# one_led.net
KiCad netlist of a schematic drawn in EAGLE
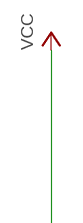
[diagram p0: schematic, sheet 1, part 1 of 2]
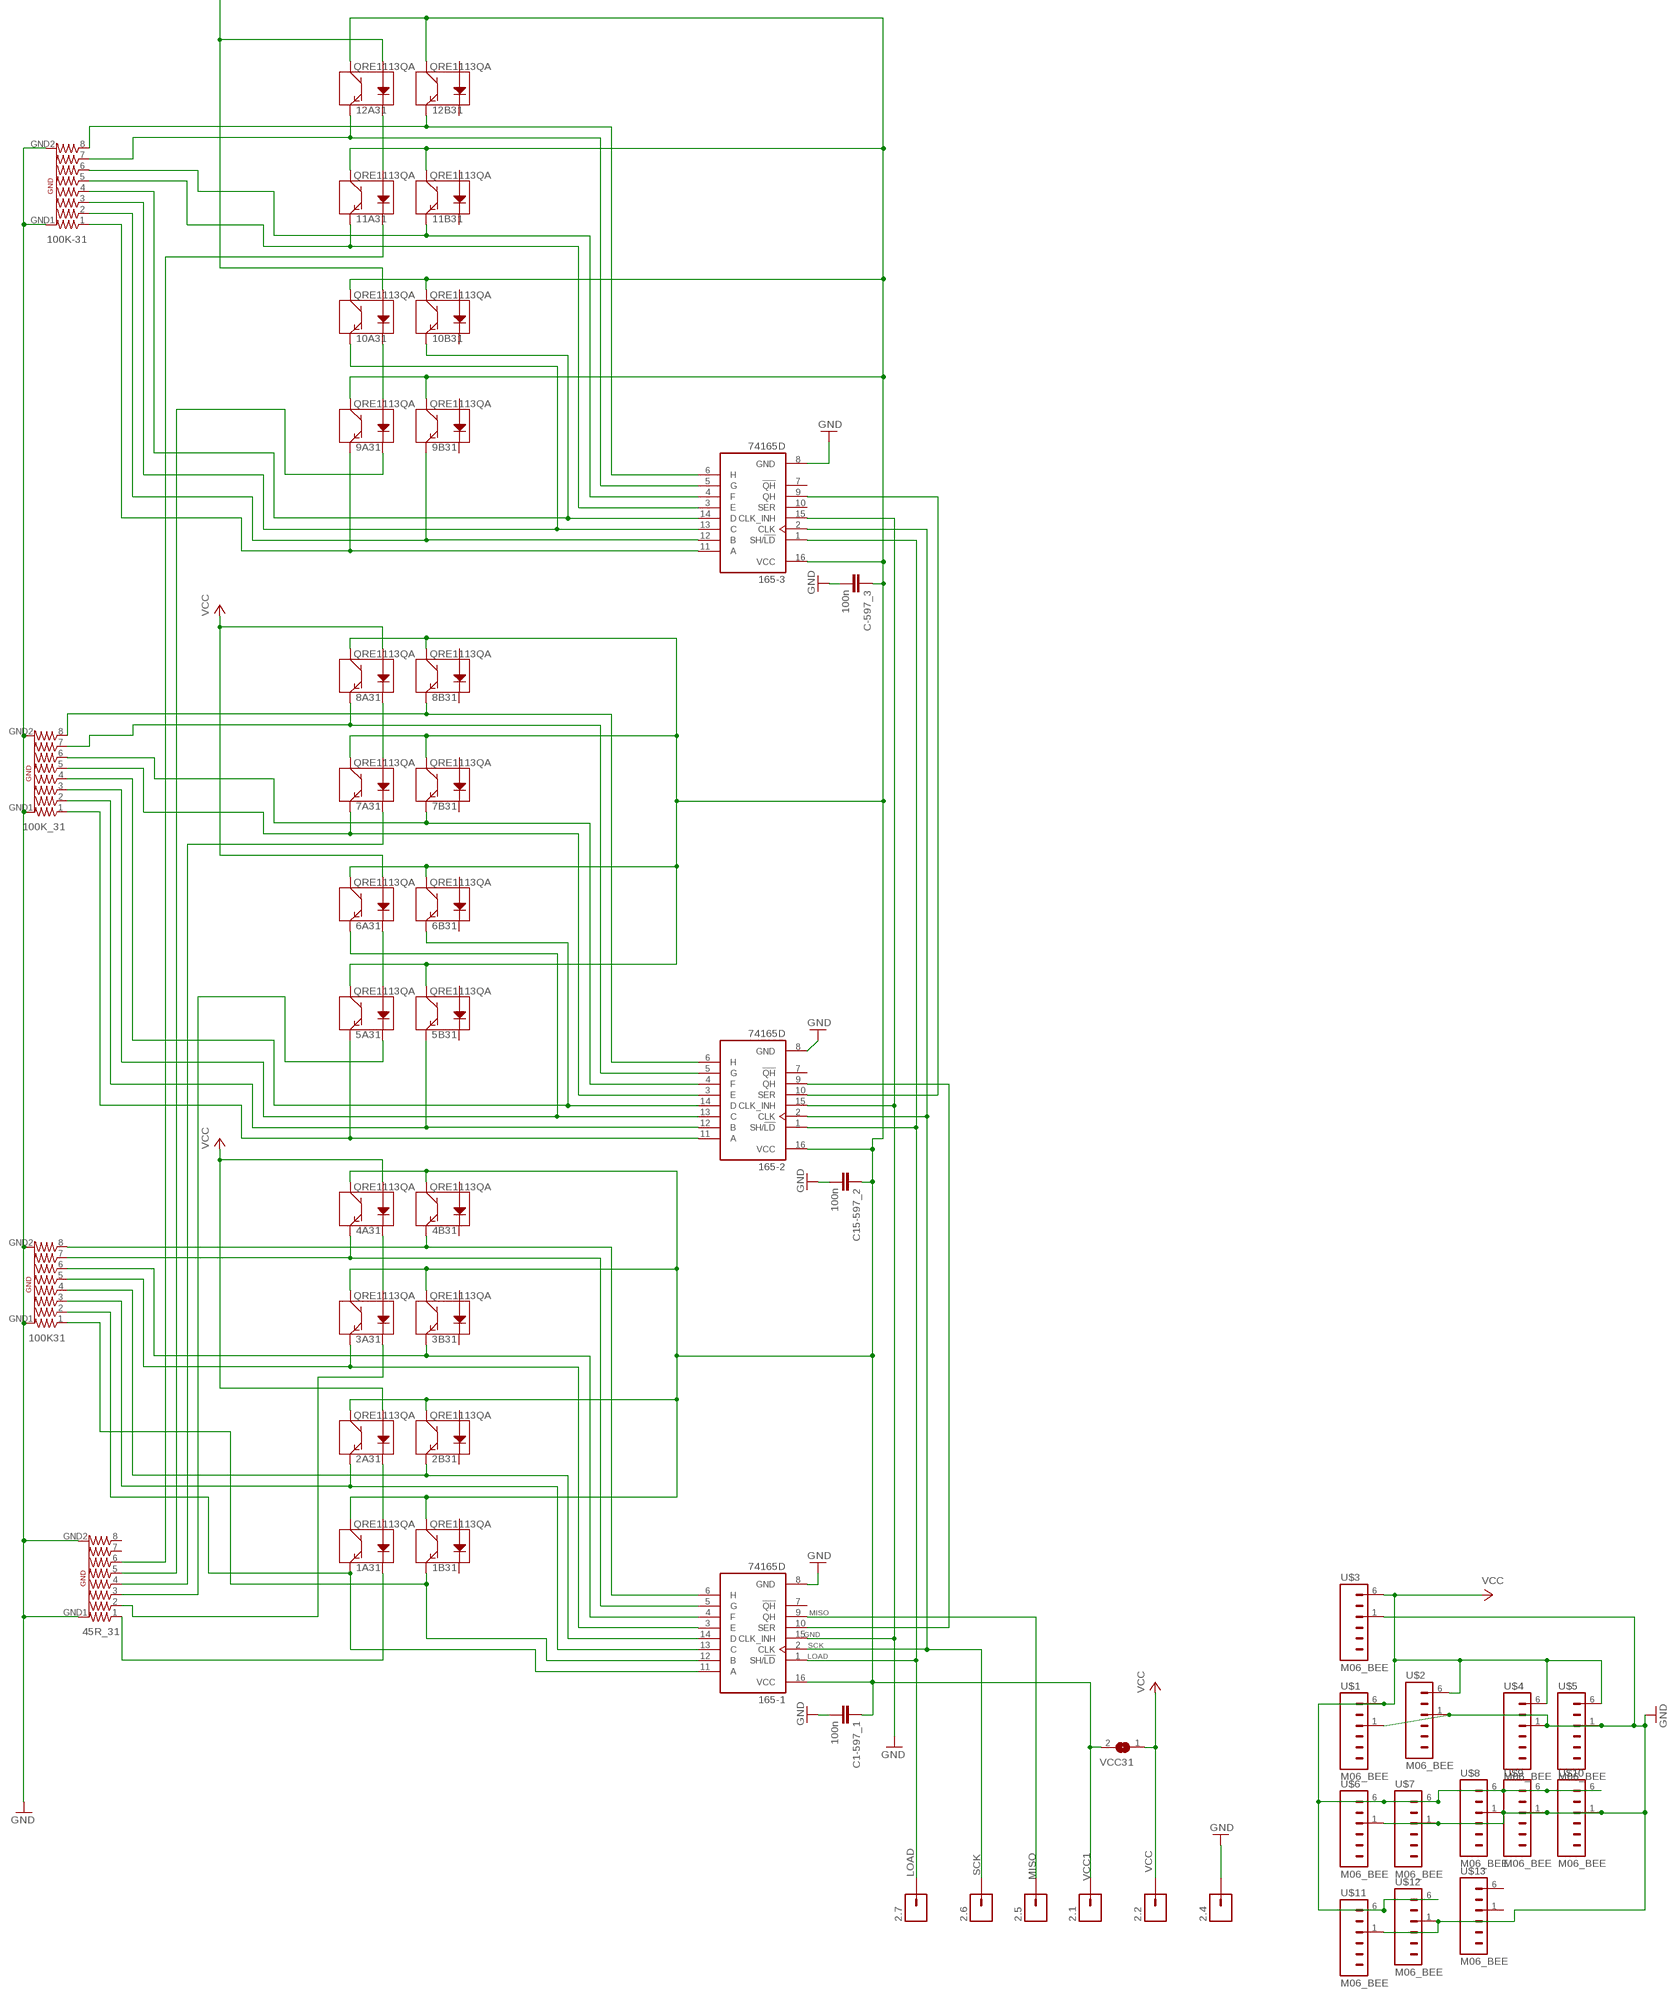
[diagram p1: schematic, sheet 1, part 2 of 2]

(export (version "E")
  (design (tool "Eeschema 10.0.6"))
  (components
    (comp (ref "1A31")
      (value "QRE1113QA")
      (footprint "eagle-import:QRE1113")
      (libsource (lib "eagle-import") (part "QRE1113QA"))
    )
    (comp (ref "1B31")
      (value "QRE1113QA")
      (footprint "eagle-import:QRE1113")
      (libsource (lib "eagle-import") (part "QRE1113QA"))
    )
    (comp (ref "2.1")
      (value "M01ADN")
      (footprint "eagle-import:1X01-16GAUGE")
      (libsource (lib "eagle-import") (part "M01ADN"))
    )
    (comp (ref "2.2")
      (value "M01ADN")
      (footprint "eagle-import:1X01-16GAUGE")
      (libsource (lib "eagle-import") (part "M01ADN"))
    )
    (comp (ref "2.4")
      (value "M01ADN")
      (footprint "eagle-import:1X01-16GAUGE")
      (libsource (lib "eagle-import") (part "M01ADN"))
    )
    (comp (ref "2.5")
      (value "M01ADN")
      (footprint "eagle-import:1X01-16GAUGE")
      (libsource (lib "eagle-import") (part "M01ADN"))
    )
    (comp (ref "2.6")
      (value "M01ADN")
      (footprint "eagle-import:1X01-16GAUGE")
      (libsource (lib "eagle-import") (part "M01ADN"))
    )
    (comp (ref "2.7")
      (value "M01ADN")
      (footprint "eagle-import:1X01-16GAUGE")
      (libsource (lib "eagle-import") (part "M01ADN"))
    )
    (comp (ref "2A31")
      (value "QRE1113QA")
      (footprint "eagle-import:QRE1113")
      (libsource (lib "eagle-import") (part "QRE1113QA"))
    )
    (comp (ref "2B31")
      (value "QRE1113QA")
      (footprint "eagle-import:QRE1113")
      (libsource (lib "eagle-import") (part "QRE1113QA"))
    )
    (comp (ref "3A31")
      (value "QRE1113QA")
      (footprint "eagle-import:QRE1113")
      (libsource (lib "eagle-import") (part "QRE1113QA"))
    )
    (comp (ref "3B31")
      (value "QRE1113QA")
      (footprint "eagle-import:QRE1113")
      (libsource (lib "eagle-import") (part "QRE1113QA"))
    )
    (comp (ref "4A31")
      (value "QRE1113QA")
      (footprint "eagle-import:QRE1113")
      (libsource (lib "eagle-import") (part "QRE1113QA"))
    )
    (comp (ref "4B31")
      (value "QRE1113QA")
      (footprint "eagle-import:QRE1113")
      (libsource (lib "eagle-import") (part "QRE1113QA"))
    )
    (comp (ref "5A31")
      (value "QRE1113QA")
      (footprint "eagle-import:QRE1113")
      (libsource (lib "eagle-import") (part "QRE1113QA"))
    )
    (comp (ref "5B31")
      (value "QRE1113QA")
      (footprint "eagle-import:QRE1113")
      (libsource (lib "eagle-import") (part "QRE1113QA"))
    )
    (comp (ref "6A31")
      (value "QRE1113QA")
      (footprint "eagle-import:QRE1113")
      (libsource (lib "eagle-import") (part "QRE1113QA"))
    )
    (comp (ref "6B31")
      (value "QRE1113QA")
      (footprint "eagle-import:QRE1113")
      (libsource (lib "eagle-import") (part "QRE1113QA"))
    )
    (comp (ref "7A31")
      (value "QRE1113QA")
      (footprint "eagle-import:QRE1113")
      (libsource (lib "eagle-import") (part "QRE1113QA"))
    )
    (comp (ref "7B31")
      (value "QRE1113QA")
      (footprint "eagle-import:QRE1113")
      (libsource (lib "eagle-import") (part "QRE1113QA"))
    )
    (comp (ref "8A31")
      (value "QRE1113QA")
      (footprint "eagle-import:QRE1113")
      (libsource (lib "eagle-import") (part "QRE1113QA"))
    )
    (comp (ref "8B31")
      (value "QRE1113QA")
      (footprint "eagle-import:QRE1113")
      (libsource (lib "eagle-import") (part "QRE1113QA"))
    )
    (comp (ref "9A31")
      (value "QRE1113QA")
      (footprint "eagle-import:QRE1113")
      (libsource (lib "eagle-import") (part "QRE1113QA"))
    )
    (comp (ref "9B31")
      (value "QRE1113QA")
      (footprint "eagle-import:QRE1113")
      (libsource (lib "eagle-import") (part "QRE1113QA"))
    )
    (comp (ref "10A31")
      (value "QRE1113QA")
      (footprint "eagle-import:QRE1113")
      (libsource (lib "eagle-import") (part "QRE1113QA"))
    )
    (comp (ref "10B31")
      (value "QRE1113QA")
      (footprint "eagle-import:QRE1113")
      (libsource (lib "eagle-import") (part "QRE1113QA"))
    )
    (comp (ref "11A31")
      (value "QRE1113QA")
      (footprint "eagle-import:QRE1113")
      (libsource (lib "eagle-import") (part "QRE1113QA"))
    )
    (comp (ref "11B31")
      (value "QRE1113QA")
      (footprint "eagle-import:QRE1113")
      (libsource (lib "eagle-import") (part "QRE1113QA"))
    )
    (comp (ref "12A31")
      (value "QRE1113QA")
      (footprint "eagle-import:QRE1113")
      (libsource (lib "eagle-import") (part "QRE1113QA"))
    )
    (comp (ref "12B31")
      (value "QRE1113QA")
      (footprint "eagle-import:QRE1113")
      (libsource (lib "eagle-import") (part "QRE1113QA"))
    )
    (comp (ref "45R_31")
      (value "RESISTOR-ARRAY_BUSSED")
      (footprint "eagle-import:1608_ARRAY")
      (libsource (lib "eagle-import") (part "RESISTOR-ARRAY_BUSSED"))
    )
    (comp (ref "100K-31")
      (value "RESISTOR-ARRAY_BUSSED")
      (footprint "eagle-import:1608_ARRAY")
      (libsource (lib "eagle-import") (part "RESISTOR-ARRAY_BUSSED"))
    )
    (comp (ref "100K31")
      (value "RESISTOR-ARRAY_BUSSED")
      (footprint "eagle-import:1608_ARRAY")
      (libsource (lib "eagle-import") (part "RESISTOR-ARRAY_BUSSED"))
    )
    (comp (ref "100K_31")
      (value "RESISTOR-ARRAY_BUSSED")
      (footprint "eagle-import:1608_ARRAY")
      (libsource (lib "eagle-import") (part "RESISTOR-ARRAY_BUSSED"))
    )
    (comp (ref "165-1")
      (value "74165D")
      (footprint "eagle-import:SO16")
      (libsource (lib "eagle-import") (part "74165D"))
    )
    (comp (ref "165-2")
      (value "74165D")
      (footprint "eagle-import:SO16")
      (libsource (lib "eagle-import") (part "74165D"))
    )
    (comp (ref "165-3")
      (value "74165D")
      (footprint "eagle-import:SO16")
      (libsource (lib "eagle-import") (part "74165D"))
    )
    (comp (ref "C-597_3")
      (value "100n")
      (footprint "eagle-import:C0603")
      (libsource (lib "eagle-import") (part "C-EUC0603"))
    )
    (comp (ref "C1-597_1")
      (value "100n")
      (footprint "eagle-import:C0603")
      (libsource (lib "eagle-import") (part "C-EUC0603"))
    )
    (comp (ref "C15-597_2")
      (value "100n")
      (footprint "eagle-import:C0603")
      (libsource (lib "eagle-import") (part "C-EUC0603"))
    )
    (comp (ref "U$1")
      (value "M06_BEE")
      (footprint "eagle-import:1X06_BEE")
      (libsource (lib "eagle-import") (part "M06_BEE"))
    )
    (comp (ref "U$2")
      (value "M06_BEE")
      (footprint "eagle-import:1X06_BEE")
      (libsource (lib "eagle-import") (part "M06_BEE"))
    )
    (comp (ref "U$3")
      (value "M06_BEE")
      (footprint "eagle-import:1X06_BEE")
      (libsource (lib "eagle-import") (part "M06_BEE"))
    )
    (comp (ref "U$4")
      (value "M06_BEE")
      (footprint "eagle-import:1X06_BEE")
      (libsource (lib "eagle-import") (part "M06_BEE"))
    )
    (comp (ref "U$5")
      (value "M06_BEE")
      (footprint "eagle-import:1X06_BEE")
      (libsource (lib "eagle-import") (part "M06_BEE"))
    )
    (comp (ref "U$6")
      (value "M06_BEE")
      (footprint "eagle-import:1X06_BEE")
      (libsource (lib "eagle-import") (part "M06_BEE"))
    )
    (comp (ref "U$7")
      (value "M06_BEE")
      (footprint "eagle-import:1X06_BEE")
      (libsource (lib "eagle-import") (part "M06_BEE"))
    )
    (comp (ref "U$8")
      (value "M06_BEE")
      (footprint "eagle-import:1X06_BEE")
      (libsource (lib "eagle-import") (part "M06_BEE"))
    )
    (comp (ref "U$9")
      (value "M06_BEE")
      (footprint "eagle-import:1X06_BEE")
      (libsource (lib "eagle-import") (part "M06_BEE"))
    )
    (comp (ref "U$10")
      (value "M06_BEE")
      (footprint "eagle-import:1X06_BEE")
      (libsource (lib "eagle-import") (part "M06_BEE"))
    )
    (comp (ref "U$11")
      (value "M06_BEE")
      (footprint "eagle-import:1X06_BEE")
      (libsource (lib "eagle-import") (part "M06_BEE"))
    )
    (comp (ref "U$12")
      (value "M06_BEE")
      (footprint "eagle-import:1X06_BEE")
      (libsource (lib "eagle-import") (part "M06_BEE"))
    )
    (comp (ref "U$13")
      (value "M06_BEE")
      (footprint "eagle-import:1X06_BEE")
      (libsource (lib "eagle-import") (part "M06_BEE"))
    )
    (comp (ref "VCC31")
      (value "SJ")
      (footprint "eagle-import:SJ")
      (libsource (lib "eagle-import") (part "SJ"))
    )
  )
  (nets
    (net (code "1") (name "/LOAD") (class "Default")
      (node (ref "165-1") (pin "1") (pinfunction "SH/~{LD}_1") (pintype "input"))
      (node (ref "165-2") (pin "1") (pinfunction "SH/~{LD}_1") (pintype "input"))
      (node (ref "165-3") (pin "1") (pinfunction "SH/~{LD}_1") (pintype "input"))
      (node (ref "2.7") (pin "1") (pinfunction "1_1") (pintype "passive"))
    )
    (net (code "2") (name "/MISO") (class "Default")
      (node (ref "165-1") (pin "9") (pinfunction "QH_9") (pintype "tri_state"))
      (node (ref "2.5") (pin "1") (pinfunction "1_1") (pintype "passive"))
    )
    (net (code "3") (name "/SCK") (class "Default")
      (node (ref "165-1") (pin "2") (pinfunction "CLK_2") (pintype "input"))
      (node (ref "165-2") (pin "2") (pinfunction "CLK_2") (pintype "input"))
      (node (ref "165-3") (pin "2") (pinfunction "CLK_2") (pintype "input"))
      (node (ref "2.6") (pin "1") (pinfunction "1_1") (pintype "passive"))
    )
    (net (code "4") (name "/VCC1") (class "Default")
      (node (ref "10A31") (pin "3") (pinfunction "C_3") (pintype "bidirectional"))
      (node (ref "10B31") (pin "3") (pinfunction "C_3") (pintype "bidirectional"))
      (node (ref "11A31") (pin "3") (pinfunction "C_3") (pintype "bidirectional"))
      (node (ref "11B31") (pin "3") (pinfunction "C_3") (pintype "bidirectional"))
      (node (ref "12A31") (pin "3") (pinfunction "C_3") (pintype "bidirectional"))
      (node (ref "12B31") (pin "3") (pinfunction "C_3") (pintype "bidirectional"))
      (node (ref "165-1") (pin "16") (pinfunction "VCC_16") (pintype "power_in"))
      (node (ref "165-2") (pin "16") (pinfunction "VCC_16") (pintype "power_in"))
      (node (ref "165-3") (pin "16") (pinfunction "VCC_16") (pintype "power_in"))
      (node (ref "1A31") (pin "3") (pinfunction "C_3") (pintype "bidirectional"))
      (node (ref "1B31") (pin "3") (pinfunction "C_3") (pintype "bidirectional"))
      (node (ref "2.1") (pin "1") (pinfunction "1_1") (pintype "passive"))
      (node (ref "2A31") (pin "3") (pinfunction "C_3") (pintype "bidirectional"))
      (node (ref "2B31") (pin "3") (pinfunction "C_3") (pintype "bidirectional"))
      (node (ref "3A31") (pin "3") (pinfunction "C_3") (pintype "bidirectional"))
      (node (ref "3B31") (pin "3") (pinfunction "C_3") (pintype "bidirectional"))
      (node (ref "4A31") (pin "3") (pinfunction "C_3") (pintype "bidirectional"))
      (node (ref "4B31") (pin "3") (pinfunction "C_3") (pintype "bidirectional"))
      (node (ref "5A31") (pin "3") (pinfunction "C_3") (pintype "bidirectional"))
      (node (ref "5B31") (pin "3") (pinfunction "C_3") (pintype "bidirectional"))
      (node (ref "6A31") (pin "3") (pinfunction "C_3") (pintype "bidirectional"))
      (node (ref "6B31") (pin "3") (pinfunction "C_3") (pintype "bidirectional"))
      (node (ref "7A31") (pin "3") (pinfunction "C_3") (pintype "bidirectional"))
      (node (ref "7B31") (pin "3") (pinfunction "C_3") (pintype "bidirectional"))
      (node (ref "8A31") (pin "3") (pinfunction "C_3") (pintype "bidirectional"))
      (node (ref "8B31") (pin "3") (pinfunction "C_3") (pintype "bidirectional"))
      (node (ref "9A31") (pin "3") (pinfunction "C_3") (pintype "bidirectional"))
      (node (ref "9B31") (pin "3") (pinfunction "C_3") (pintype "bidirectional"))
      (node (ref "C-597_3") (pin "1") (pinfunction "1_1") (pintype "passive"))
      (node (ref "C1-597_1") (pin "1") (pinfunction "1_1") (pintype "passive"))
      (node (ref "C15-597_2") (pin "1") (pinfunction "1_1") (pintype "passive"))
      (node (ref "VCC31") (pin "2") (pinfunction "2_2") (pintype "passive"))
    )
    (net (code "5") (name "GND") (class "Default")
      (node (ref "100K-31") (pin "GND1") (pinfunction "GND1_GND1") (pintype "passive"))
      (node (ref "100K-31") (pin "GND2") (pinfunction "GND2_GND2") (pintype "passive"))
      (node (ref "100K31") (pin "GND1") (pinfunction "GND1_GND1") (pintype "passive"))
      (node (ref "100K31") (pin "GND2") (pinfunction "GND2_GND2") (pintype "passive"))
      (node (ref "100K_31") (pin "GND1") (pinfunction "GND1_GND1") (pintype "passive"))
      (node (ref "100K_31") (pin "GND2") (pinfunction "GND2_GND2") (pintype "passive"))
      (node (ref "165-1") (pin "15") (pinfunction "CLK_INH_15") (pintype "input"))
      (node (ref "165-1") (pin "8") (pinfunction "GND_8") (pintype "power_in"))
      (node (ref "165-2") (pin "15") (pinfunction "CLK_INH_15") (pintype "input"))
      (node (ref "165-2") (pin "8") (pinfunction "GND_8") (pintype "power_in"))
      (node (ref "165-3") (pin "15") (pinfunction "CLK_INH_15") (pintype "input"))
      (node (ref "165-3") (pin "8") (pinfunction "GND_8") (pintype "power_in"))
      (node (ref "2.4") (pin "1") (pinfunction "1_1") (pintype "passive"))
      (node (ref "45R_31") (pin "GND1") (pinfunction "GND1_GND1") (pintype "passive"))
      (node (ref "45R_31") (pin "GND2") (pinfunction "GND2_GND2") (pintype "passive"))
      (node (ref "C-597_3") (pin "2") (pinfunction "2_2") (pintype "passive"))
      (node (ref "C1-597_1") (pin "2") (pinfunction "2_2") (pintype "passive"))
      (node (ref "C15-597_2") (pin "2") (pinfunction "2_2") (pintype "passive"))
      (node (ref "U$1") (pin "1") (pinfunction "4_1") (pintype "passive"))
      (node (ref "U$10") (pin "1") (pinfunction "4_1") (pintype "passive"))
      (node (ref "U$11") (pin "1") (pinfunction "4_1") (pintype "passive"))
      (node (ref "U$12") (pin "1") (pinfunction "4_1") (pintype "passive"))
      (node (ref "U$2") (pin "1") (pinfunction "4_1") (pintype "passive"))
      (node (ref "U$3") (pin "1") (pinfunction "4_1") (pintype "passive"))
      (node (ref "U$4") (pin "1") (pinfunction "4_1") (pintype "passive"))
      (node (ref "U$5") (pin "1") (pinfunction "4_1") (pintype "passive"))
      (node (ref "U$6") (pin "1") (pinfunction "4_1") (pintype "passive"))
      (node (ref "U$7") (pin "1") (pinfunction "4_1") (pintype "passive"))
      (node (ref "U$8") (pin "1") (pinfunction "4_1") (pintype "passive"))
      (node (ref "U$9") (pin "1") (pinfunction "4_1") (pintype "passive"))
    )
    (net (code "6") (name "Net-(1A31-A)") (class "Default")
      (node (ref "1A31") (pin "1") (pinfunction "A_1") (pintype "bidirectional"))
      (node (ref "2A31") (pin "2") (pinfunction "K_2") (pintype "bidirectional"))
    )
    (net (code "7") (name "Net-(1A31-K)") (class "Default")
      (node (ref "1A31") (pin "2") (pinfunction "K_2") (pintype "bidirectional"))
      (node (ref "45R_31") (pin "1") (pinfunction "1_1") (pintype "passive"))
    )
    (net (code "8") (name "Net-(3A31-A)") (class "Default")
      (node (ref "3A31") (pin "1") (pinfunction "A_1") (pintype "bidirectional"))
      (node (ref "4A31") (pin "2") (pinfunction "K_2") (pintype "bidirectional"))
    )
    (net (code "9") (name "Net-(3A31-K)") (class "Default")
      (node (ref "3A31") (pin "2") (pinfunction "K_2") (pintype "bidirectional"))
      (node (ref "45R_31") (pin "2") (pinfunction "2_2") (pintype "passive"))
    )
    (net (code "10") (name "Net-(5A31-A)") (class "Default")
      (node (ref "5A31") (pin "1") (pinfunction "A_1") (pintype "bidirectional"))
      (node (ref "6A31") (pin "2") (pinfunction "K_2") (pintype "bidirectional"))
    )
    (net (code "11") (name "Net-(5A31-K)") (class "Default")
      (node (ref "45R_31") (pin "3") (pinfunction "3_3") (pintype "passive"))
      (node (ref "5A31") (pin "2") (pinfunction "K_2") (pintype "bidirectional"))
    )
    (net (code "12") (name "Net-(7A31-A)") (class "Default")
      (node (ref "7A31") (pin "1") (pinfunction "A_1") (pintype "bidirectional"))
      (node (ref "8A31") (pin "2") (pinfunction "K_2") (pintype "bidirectional"))
    )
    (net (code "13") (name "Net-(7A31-K)") (class "Default")
      (node (ref "45R_31") (pin "4") (pinfunction "4_4") (pintype "passive"))
      (node (ref "7A31") (pin "2") (pinfunction "K_2") (pintype "bidirectional"))
    )
    (net (code "14") (name "Net-(9A31-K)") (class "Default")
      (node (ref "45R_31") (pin "5") (pinfunction "5_5") (pintype "passive"))
      (node (ref "9A31") (pin "2") (pinfunction "K_2") (pintype "bidirectional"))
    )
    (net (code "15") (name "Net-(10A31-E)") (class "Default")
      (node (ref "100K-31") (pin "3") (pinfunction "3_3") (pintype "passive"))
      (node (ref "10A31") (pin "4") (pinfunction "E_4") (pintype "bidirectional"))
      (node (ref "165-3") (pin "13") (pinfunction "C_13") (pintype "tri_state"))
    )
    (net (code "16") (name "Net-(10A31-K)") (class "Default")
      (node (ref "10A31") (pin "2") (pinfunction "K_2") (pintype "bidirectional"))
      (node (ref "9A31") (pin "1") (pinfunction "A_1") (pintype "bidirectional"))
    )
    (net (code "17") (name "Net-(10B31-E)") (class "Default")
      (node (ref "100K-31") (pin "4") (pinfunction "4_4") (pintype "passive"))
      (node (ref "10B31") (pin "4") (pinfunction "E_4") (pintype "bidirectional"))
      (node (ref "165-3") (pin "14") (pinfunction "D_14") (pintype "tri_state"))
    )
    (net (code "18") (name "Net-(11A31-A)") (class "Default")
      (node (ref "11A31") (pin "1") (pinfunction "A_1") (pintype "bidirectional"))
      (node (ref "12A31") (pin "2") (pinfunction "K_2") (pintype "bidirectional"))
    )
    (net (code "19") (name "Net-(11A31-E)") (class "Default")
      (node (ref "100K-31") (pin "5") (pinfunction "5_5") (pintype "passive"))
      (node (ref "11A31") (pin "4") (pinfunction "E_4") (pintype "bidirectional"))
      (node (ref "165-3") (pin "3") (pinfunction "E_3") (pintype "tri_state"))
    )
    (net (code "20") (name "Net-(11A31-K)") (class "Default")
      (node (ref "11A31") (pin "2") (pinfunction "K_2") (pintype "bidirectional"))
      (node (ref "45R_31") (pin "6") (pinfunction "6_6") (pintype "passive"))
    )
    (net (code "21") (name "Net-(11B31-E)") (class "Default")
      (node (ref "100K-31") (pin "6") (pinfunction "6_6") (pintype "passive"))
      (node (ref "11B31") (pin "4") (pinfunction "E_4") (pintype "bidirectional"))
      (node (ref "165-3") (pin "4") (pinfunction "F_4") (pintype "tri_state"))
    )
    (net (code "22") (name "Net-(12A31-E)") (class "Default")
      (node (ref "100K-31") (pin "7") (pinfunction "7_7") (pintype "passive"))
      (node (ref "12A31") (pin "4") (pinfunction "E_4") (pintype "bidirectional"))
      (node (ref "165-3") (pin "5") (pinfunction "G_5") (pintype "tri_state"))
    )
    (net (code "23") (name "Net-(12B31-E)") (class "Default")
      (node (ref "100K-31") (pin "8") (pinfunction "8_8") (pintype "passive"))
      (node (ref "12B31") (pin "4") (pinfunction "E_4") (pintype "bidirectional"))
      (node (ref "165-3") (pin "6") (pinfunction "H_6") (pintype "tri_state"))
    )
    (net (code "24") (name "Net-(165-1-A)") (class "Default")
      (node (ref "100K31") (pin "2") (pinfunction "2_2") (pintype "passive"))
      (node (ref "165-1") (pin "11") (pinfunction "A_11") (pintype "tri_state"))
      (node (ref "1A31") (pin "4") (pinfunction "E_4") (pintype "bidirectional"))
    )
    (net (code "25") (name "Net-(165-1-B)") (class "Default")
      (node (ref "100K31") (pin "1") (pinfunction "1_1") (pintype "passive"))
      (node (ref "165-1") (pin "12") (pinfunction "B_12") (pintype "tri_state"))
      (node (ref "1B31") (pin "4") (pinfunction "E_4") (pintype "bidirectional"))
    )
    (net (code "26") (name "Net-(165-1-C)") (class "Default")
      (node (ref "100K31") (pin "3") (pinfunction "3_3") (pintype "passive"))
      (node (ref "165-1") (pin "13") (pinfunction "C_13") (pintype "tri_state"))
      (node (ref "2A31") (pin "4") (pinfunction "E_4") (pintype "bidirectional"))
    )
    (net (code "27") (name "Net-(165-1-D)") (class "Default")
      (node (ref "100K31") (pin "4") (pinfunction "4_4") (pintype "passive"))
      (node (ref "165-1") (pin "14") (pinfunction "D_14") (pintype "tri_state"))
      (node (ref "2B31") (pin "4") (pinfunction "E_4") (pintype "bidirectional"))
    )
    (net (code "28") (name "Net-(165-1-E)") (class "Default")
      (node (ref "100K31") (pin "5") (pinfunction "5_5") (pintype "passive"))
      (node (ref "165-1") (pin "3") (pinfunction "E_3") (pintype "tri_state"))
      (node (ref "3A31") (pin "4") (pinfunction "E_4") (pintype "bidirectional"))
    )
    (net (code "29") (name "Net-(165-1-F)") (class "Default")
      (node (ref "100K31") (pin "6") (pinfunction "6_6") (pintype "passive"))
      (node (ref "165-1") (pin "4") (pinfunction "F_4") (pintype "tri_state"))
      (node (ref "3B31") (pin "4") (pinfunction "E_4") (pintype "bidirectional"))
    )
    (net (code "30") (name "Net-(165-1-G)") (class "Default")
      (node (ref "100K31") (pin "7") (pinfunction "7_7") (pintype "passive"))
      (node (ref "165-1") (pin "5") (pinfunction "G_5") (pintype "tri_state"))
      (node (ref "4A31") (pin "4") (pinfunction "E_4") (pintype "bidirectional"))
    )
    (net (code "31") (name "Net-(165-1-H)") (class "Default")
      (node (ref "100K31") (pin "8") (pinfunction "8_8") (pintype "passive"))
      (node (ref "165-1") (pin "6") (pinfunction "H_6") (pintype "tri_state"))
      (node (ref "4B31") (pin "4") (pinfunction "E_4") (pintype "bidirectional"))
    )
    (net (code "32") (name "Net-(165-1-SER)") (class "Default")
      (node (ref "165-1") (pin "10") (pinfunction "SER_10") (pintype "input"))
      (node (ref "165-2") (pin "9") (pinfunction "QH_9") (pintype "tri_state"))
    )
    (net (code "33") (name "Net-(165-2-A)") (class "Default")
      (node (ref "100K_31") (pin "1") (pinfunction "1_1") (pintype "passive"))
      (node (ref "165-2") (pin "11") (pinfunction "A_11") (pintype "tri_state"))
      (node (ref "5A31") (pin "4") (pinfunction "E_4") (pintype "bidirectional"))
    )
    (net (code "34") (name "Net-(165-2-B)") (class "Default")
      (node (ref "100K_31") (pin "2") (pinfunction "2_2") (pintype "passive"))
      (node (ref "165-2") (pin "12") (pinfunction "B_12") (pintype "tri_state"))
      (node (ref "5B31") (pin "4") (pinfunction "E_4") (pintype "bidirectional"))
    )
    (net (code "35") (name "Net-(165-2-C)") (class "Default")
      (node (ref "100K_31") (pin "3") (pinfunction "3_3") (pintype "passive"))
      (node (ref "165-2") (pin "13") (pinfunction "C_13") (pintype "tri_state"))
      (node (ref "6A31") (pin "4") (pinfunction "E_4") (pintype "bidirectional"))
    )
    (net (code "36") (name "Net-(165-2-D)") (class "Default")
      (node (ref "100K_31") (pin "4") (pinfunction "4_4") (pintype "passive"))
      (node (ref "165-2") (pin "14") (pinfunction "D_14") (pintype "tri_state"))
      (node (ref "6B31") (pin "4") (pinfunction "E_4") (pintype "bidirectional"))
    )
    (net (code "37") (name "Net-(165-2-E)") (class "Default")
      (node (ref "100K_31") (pin "5") (pinfunction "5_5") (pintype "passive"))
      (node (ref "165-2") (pin "3") (pinfunction "E_3") (pintype "tri_state"))
      (node (ref "7A31") (pin "4") (pinfunction "E_4") (pintype "bidirectional"))
    )
    (net (code "38") (name "Net-(165-2-F)") (class "Default")
      (node (ref "100K_31") (pin "6") (pinfunction "6_6") (pintype "passive"))
      (node (ref "165-2") (pin "4") (pinfunction "F_4") (pintype "tri_state"))
      (node (ref "7B31") (pin "4") (pinfunction "E_4") (pintype "bidirectional"))
    )
    (net (code "39") (name "Net-(165-2-G)") (class "Default")
      (node (ref "100K_31") (pin "7") (pinfunction "7_7") (pintype "passive"))
      (node (ref "165-2") (pin "5") (pinfunction "G_5") (pintype "tri_state"))
      (node (ref "8A31") (pin "4") (pinfunction "E_4") (pintype "bidirectional"))
    )
    (net (code "40") (name "Net-(165-2-H)") (class "Default")
      (node (ref "100K_31") (pin "8") (pinfunction "8_8") (pintype "passive"))
      (node (ref "165-2") (pin "6") (pinfunction "H_6") (pintype "tri_state"))
      (node (ref "8B31") (pin "4") (pinfunction "E_4") (pintype "bidirectional"))
    )
    (net (code "41") (name "Net-(165-2-SER)") (class "Default")
      (node (ref "165-2") (pin "10") (pinfunction "SER_10") (pintype "input"))
      (node (ref "165-3") (pin "9") (pinfunction "QH_9") (pintype "tri_state"))
    )
    (net (code "42") (name "Net-(165-3-A)") (class "Default")
      (node (ref "100K-31") (pin "1") (pinfunction "1_1") (pintype "passive"))
      (node (ref "165-3") (pin "11") (pinfunction "A_11") (pintype "tri_state"))
      (node (ref "9A31") (pin "4") (pinfunction "E_4") (pintype "bidirectional"))
    )
    (net (code "43") (name "Net-(165-3-B)") (class "Default")
      (node (ref "100K-31") (pin "2") (pinfunction "2_2") (pintype "passive"))
      (node (ref "165-3") (pin "12") (pinfunction "B_12") (pintype "tri_state"))
      (node (ref "9B31") (pin "4") (pinfunction "E_4") (pintype "bidirectional"))
    )
    (net (code "44") (name "VCC") (class "Default")
      (node (ref "10A31") (pin "1") (pinfunction "A_1") (pintype "bidirectional"))
      (node (ref "12A31") (pin "1") (pinfunction "A_1") (pintype "bidirectional"))
      (node (ref "2.2") (pin "1") (pinfunction "1_1") (pintype "passive"))
      (node (ref "2A31") (pin "1") (pinfunction "A_1") (pintype "bidirectional"))
      (node (ref "4A31") (pin "1") (pinfunction "A_1") (pintype "bidirectional"))
      (node (ref "6A31") (pin "1") (pinfunction "A_1") (pintype "bidirectional"))
      (node (ref "8A31") (pin "1") (pinfunction "A_1") (pintype "bidirectional"))
      (node (ref "U$1") (pin "6") (pinfunction "6_6") (pintype "passive"))
      (node (ref "U$10") (pin "6") (pinfunction "6_6") (pintype "passive"))
      (node (ref "U$11") (pin "6") (pinfunction "6_6") (pintype "passive"))
      (node (ref "U$12") (pin "6") (pinfunction "6_6") (pintype "passive"))
      (node (ref "U$2") (pin "6") (pinfunction "6_6") (pintype "passive"))
      (node (ref "U$3") (pin "6") (pinfunction "6_6") (pintype "passive"))
      (node (ref "U$4") (pin "6") (pinfunction "6_6") (pintype "passive"))
      (node (ref "U$5") (pin "6") (pinfunction "6_6") (pintype "passive"))
      (node (ref "U$6") (pin "6") (pinfunction "6_6") (pintype "passive"))
      (node (ref "U$7") (pin "6") (pinfunction "6_6") (pintype "passive"))
      (node (ref "U$8") (pin "6") (pinfunction "6_6") (pintype "passive"))
      (node (ref "U$9") (pin "6") (pinfunction "6_6") (pintype "passive"))
      (node (ref "VCC31") (pin "1") (pinfunction "1_1") (pintype "passive"))
    )
    (net (code "45") (name "unconnected-(1B31-A-Pad1)") (class "Default")
      (node (ref "1B31") (pin "1") (pinfunction "A_1") (pintype "bidirectional"))
    )
    (net (code "46") (name "unconnected-(1B31-K-Pad2)") (class "Default")
      (node (ref "1B31") (pin "2") (pinfunction "K_2") (pintype "bidirectional"))
    )
    (net (code "47") (name "unconnected-(2B31-A-Pad1)") (class "Default")
      (node (ref "2B31") (pin "1") (pinfunction "A_1") (pintype "bidirectional"))
    )
    (net (code "48") (name "unconnected-(2B31-K-Pad2)") (class "Default")
      (node (ref "2B31") (pin "2") (pinfunction "K_2") (pintype "bidirectional"))
    )
    (net (code "49") (name "unconnected-(3B31-A-Pad1)") (class "Default")
      (node (ref "3B31") (pin "1") (pinfunction "A_1") (pintype "bidirectional"))
    )
    (net (code "50") (name "unconnected-(3B31-K-Pad2)") (class "Default")
      (node (ref "3B31") (pin "2") (pinfunction "K_2") (pintype "bidirectional"))
    )
    (net (code "51") (name "unconnected-(4B31-A-Pad1)") (class "Default")
      (node (ref "4B31") (pin "1") (pinfunction "A_1") (pintype "bidirectional"))
    )
    (net (code "52") (name "unconnected-(4B31-K-Pad2)") (class "Default")
      (node (ref "4B31") (pin "2") (pinfunction "K_2") (pintype "bidirectional"))
    )
    (net (code "53") (name "unconnected-(5B31-A-Pad1)") (class "Default")
      (node (ref "5B31") (pin "1") (pinfunction "A_1") (pintype "bidirectional"))
    )
    (net (code "54") (name "unconnected-(5B31-K-Pad2)") (class "Default")
      (node (ref "5B31") (pin "2") (pinfunction "K_2") (pintype "bidirectional"))
    )
    (net (code "55") (name "unconnected-(6B31-A-Pad1)") (class "Default")
      (node (ref "6B31") (pin "1") (pinfunction "A_1") (pintype "bidirectional"))
    )
    (net (code "56") (name "unconnected-(6B31-K-Pad2)") (class "Default")
      (node (ref "6B31") (pin "2") (pinfunction "K_2") (pintype "bidirectional"))
    )
    (net (code "57") (name "unconnected-(7B31-A-Pad1)") (class "Default")
      (node (ref "7B31") (pin "1") (pinfunction "A_1") (pintype "bidirectional"))
    )
    (net (code "58") (name "unconnected-(7B31-K-Pad2)") (class "Default")
      (node (ref "7B31") (pin "2") (pinfunction "K_2") (pintype "bidirectional"))
    )
    (net (code "59") (name "unconnected-(8B31-A-Pad1)") (class "Default")
      (node (ref "8B31") (pin "1") (pinfunction "A_1") (pintype "bidirectional"))
    )
    (net (code "60") (name "unconnected-(8B31-K-Pad2)") (class "Default")
      (node (ref "8B31") (pin "2") (pinfunction "K_2") (pintype "bidirectional"))
    )
    (net (code "61") (name "unconnected-(9B31-A-Pad1)") (class "Default")
      (node (ref "9B31") (pin "1") (pinfunction "A_1") (pintype "bidirectional"))
    )
    (net (code "62") (name "unconnected-(9B31-K-Pad2)") (class "Default")
      (node (ref "9B31") (pin "2") (pinfunction "K_2") (pintype "bidirectional"))
    )
    (net (code "63") (name "unconnected-(10B31-A-Pad1)") (class "Default")
      (node (ref "10B31") (pin "1") (pinfunction "A_1") (pintype "bidirectional"))
    )
    (net (code "64") (name "unconnected-(10B31-K-Pad2)") (class "Default")
      (node (ref "10B31") (pin "2") (pinfunction "K_2") (pintype "bidirectional"))
    )
    (net (code "65") (name "unconnected-(11B31-A-Pad1)") (class "Default")
      (node (ref "11B31") (pin "1") (pinfunction "A_1") (pintype "bidirectional"))
    )
    (net (code "66") (name "unconnected-(11B31-K-Pad2)") (class "Default")
      (node (ref "11B31") (pin "2") (pinfunction "K_2") (pintype "bidirectional"))
    )
    (net (code "67") (name "unconnected-(12B31-A-Pad1)") (class "Default")
      (node (ref "12B31") (pin "1") (pinfunction "A_1") (pintype "bidirectional"))
    )
    (net (code "68") (name "unconnected-(12B31-K-Pad2)") (class "Default")
      (node (ref "12B31") (pin "2") (pinfunction "K_2") (pintype "bidirectional"))
    )
    (net (code "69") (name "unconnected-(45R_31-Pad7)") (class "Default")
      (node (ref "45R_31") (pin "7") (pinfunction "7_7") (pintype "passive"))
    )
    (net (code "70") (name "unconnected-(45R_31-Pad8)") (class "Default")
      (node (ref "45R_31") (pin "8") (pinfunction "8_8") (pintype "passive"))
    )
    (net (code "71") (name "unconnected-(165-1-~{QH}-Pad7)") (class "Default")
      (node (ref "165-1") (pin "7") (pinfunction "~{QH}_7") (pintype "input"))
    )
    (net (code "72") (name "unconnected-(165-2-~{QH}-Pad7)") (class "Default")
      (node (ref "165-2") (pin "7") (pinfunction "~{QH}_7") (pintype "input"))
    )
    (net (code "73") (name "unconnected-(165-3-SER-Pad10)") (class "Default")
      (node (ref "165-3") (pin "10") (pinfunction "SER_10") (pintype "input"))
    )
    (net (code "74") (name "unconnected-(165-3-~{QH}-Pad7)") (class "Default")
      (node (ref "165-3") (pin "7") (pinfunction "~{QH}_7") (pintype "input"))
    )
    (net (code "75") (name "unconnected-(U$13-4-Pad1)") (class "Default")
      (node (ref "U$13") (pin "1") (pinfunction "4_1") (pintype "passive"))
    )
    (net (code "76") (name "unconnected-(U$13-Pad6)") (class "Default")
      (node (ref "U$13") (pin "6") (pinfunction "6_6") (pintype "passive"))
    )
  )
)
